# Motor_Driver.net
KiCad netlist of a schematic drawn in Altium Designer
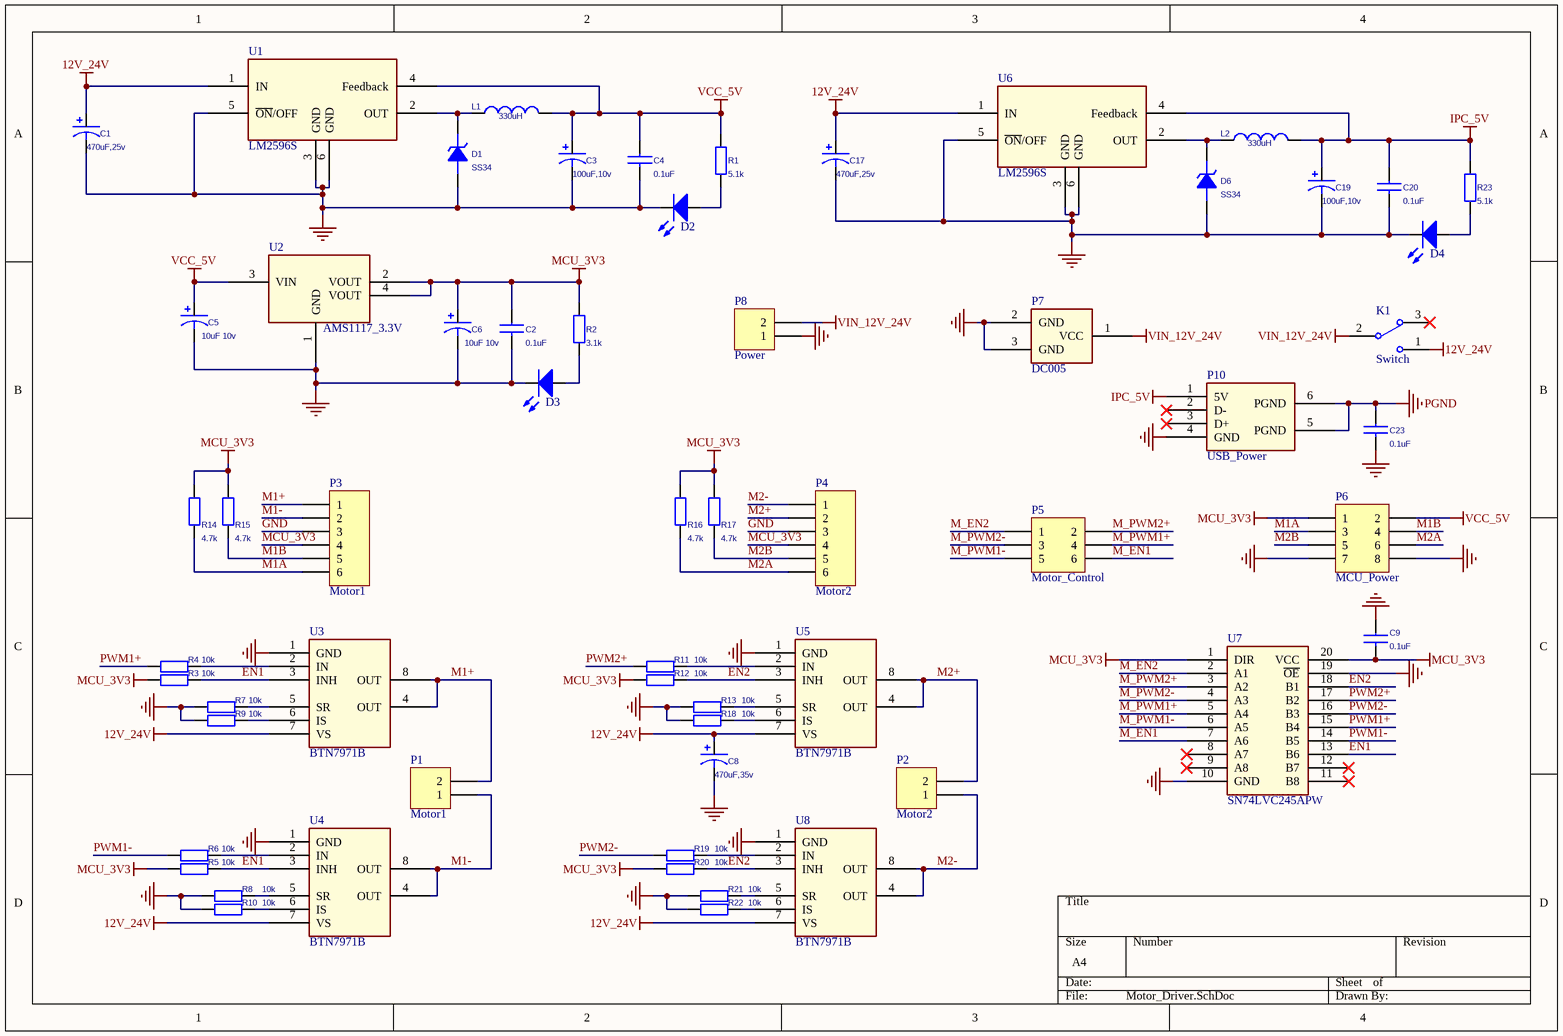
[diagram p0: Motor_Driver.SchDoc]

(export (version "E")
  (design (tool "Eeschema 10.0.6"))
  (components
    (comp (ref "C1")
      (value "470uF,25v")
      (footprint "SMD8102_C")
      (libsource (lib "My_Library") (part "Cap_Polar"))
    )
    (comp (ref "C2") (value "0.1uF") (libsource (lib "My_Library") (part "Cap")))
    (comp (ref "C3")
      (value "100uF,10v")
      (footprint "CAP_CASE_C_6032")
      (libsource (lib "My_Library") (part "Cap_Polar"))
    )
    (comp (ref "C4") (value "0.1uF") (libsource (lib "My_Library") (part "Cap")))
    (comp (ref "C5")
      (value "10uF 10v")
      (footprint "CAP_CASE_A_3216")
      (libsource (lib "My_Library") (part "Cap_Polar"))
    )
    (comp (ref "C6")
      (value "10uF 10v")
      (footprint "CAP_CASE_A_3216")
      (libsource (lib "My_Library") (part "Cap_Polar"))
    )
    (comp (ref "C8")
      (value "470uF,35v")
      (footprint "SMD8102_C")
      (libsource (lib "My_Library") (part "Cap_Polar"))
    )
    (comp (ref "C9") (value "0.1uF") (libsource (lib "My_Library") (part "Cap")))
    (comp (ref "C17")
      (value "470uF,25v")
      (footprint "SMD8102_C")
      (libsource (lib "My_Library") (part "Cap_Polar"))
    )
    (comp (ref "C19")
      (value "100uF,10v")
      (footprint "CAP_CASE_C_6032")
      (libsource (lib "My_Library") (part "Cap_Polar"))
    )
    (comp (ref "C20") (value "0.1uF") (libsource (lib "My_Library") (part "Cap")))
    (comp (ref "C23") (value "0.1uF") (libsource (lib "My_Library") (part "Cap")))
    (comp (ref "D1") (value "SS34") (libsource (lib "My_Library") (part "Diode_Zener")))
    (comp (ref "D2") (value "LED_0603") (footprint "0603_LED") (libsource (lib "My_Library") (part "LED")))
    (comp (ref "D3") (value "LED_0603") (footprint "0603_LED") (libsource (lib "My_Library") (part "LED")))
    (comp (ref "D4") (value "LED_0603") (footprint "0603_LED") (libsource (lib "My_Library") (part "LED")))
    (comp (ref "D6") (value "SS34") (libsource (lib "My_Library") (part "Diode_Zener")))
    (comp (ref "K1")
      (value "Switch")
      (footprint "Switch_Key3")
      (libsource (lib "My_Library") (part "Switch_Key3"))
    )
    (comp (ref "L1") (value "330uH") (libsource (lib "My_Library") (part "Inductor")))
    (comp (ref "L2") (value "330uH") (libsource (lib "My_Library") (part "Inductor")))
    (comp (ref "P1")
      (value "Motor1")
      (footprint "HT3.96_Power")
      (libsource (lib "My_Library") (part "HT3.96_Power"))
    )
    (comp (ref "P2")
      (value "Motor2")
      (footprint "HT3.96_Power")
      (libsource (lib "My_Library") (part "HT3.96_Power"))
    )
    (comp (ref "P3") (value "Motor1") (footprint "PH2.0_P6") (libsource (lib "My_Library") (part "PH2.0_P6")))
    (comp (ref "P4") (value "Motor2") (footprint "PH2.0_P6") (libsource (lib "My_Library") (part "PH2.0_P6")))
    (comp (ref "P5")
      (value "Motor_Control")
      (footprint "Connect_3×2")
      (libsource (lib "My_Library") (part "Connect_3×2"))
    )
    (comp (ref "P6")
      (value "MCU_Power")
      (footprint "CONNECT_4×2")
      (libsource (lib "My_Library") (part "Connect_4×2"))
    )
    (comp (ref "P7") (value "DC005") (footprint "DC005") (libsource (lib "My_Library") (part "DC005")))
    (comp (ref "P8")
      (value "Power")
      (footprint "HT3.96_Power")
      (libsource (lib "My_Library") (part "HT3.96_Power"))
    )
    (comp (ref "P10")
      (value "USB_Power")
      (footprint "USB_Pin6")
      (libsource (lib "My_Library") (part "USB_Pin6"))
    )
    (comp (ref "R1") (value "5.1k") (footprint "0805_R") (libsource (lib "My_Library") (part "Res")))
    (comp (ref "R2") (value "3.1k") (footprint "0805_R") (libsource (lib "My_Library") (part "Res")))
    (comp (ref "R3") (value "10k") (footprint "0805_R") (libsource (lib "") (part "Res_1")))
    (comp (ref "R4") (value "10k") (footprint "0805_R") (libsource (lib "") (part "Res_1")))
    (comp (ref "R5") (value "10k") (footprint "0805_R") (libsource (lib "") (part "Res_2")))
    (comp (ref "R6") (value "10k") (footprint "0805_R") (libsource (lib "") (part "Res_2")))
    (comp (ref "R7") (value "10k") (footprint "0805_R") (libsource (lib "") (part "Res_1")))
    (comp (ref "R8") (value "10k") (footprint "0805_R") (libsource (lib "") (part "Res_2")))
    (comp (ref "R9") (value "10k") (footprint "0805_R") (libsource (lib "") (part "Res_1")))
    (comp (ref "R10") (value "10k") (footprint "0805_R") (libsource (lib "") (part "Res_2")))
    (comp (ref "R11") (value "10k") (footprint "0805_R") (libsource (lib "") (part "Res_1")))
    (comp (ref "R12") (value "10k") (footprint "0805_R") (libsource (lib "") (part "Res_1")))
    (comp (ref "R13") (value "10k") (footprint "0805_R") (libsource (lib "") (part "Res_1")))
    (comp (ref "R14") (value "4.7k") (footprint "0805_R") (libsource (lib "My_Library") (part "Res")))
    (comp (ref "R15") (value "4.7k") (footprint "0805_R") (libsource (lib "My_Library") (part "Res")))
    (comp (ref "R16") (value "4.7k") (footprint "0805_R") (libsource (lib "My_Library") (part "Res")))
    (comp (ref "R17") (value "4.7k") (footprint "0805_R") (libsource (lib "My_Library") (part "Res")))
    (comp (ref "R18") (value "10k") (footprint "0805_R") (libsource (lib "") (part "Res_1")))
    (comp (ref "R19") (value "10k") (footprint "0805_R") (libsource (lib "") (part "Res_2")))
    (comp (ref "R20") (value "10k") (footprint "0805_R") (libsource (lib "") (part "Res_2")))
    (comp (ref "R21") (value "10k") (footprint "0805_R") (libsource (lib "") (part "Res_2")))
    (comp (ref "R22") (value "10k") (footprint "0805_R") (libsource (lib "") (part "Res_2")))
    (comp (ref "R23") (value "5.1k") (footprint "0805_R") (libsource (lib "My_Library") (part "Res")))
    (comp (ref "U1") (value "LM2596S") (footprint "LM2596S") (libsource (lib "My_Library") (part "LM2596S")))
    (comp (ref "U2")
      (value "AMS1117_3.3V")
      (footprint "LM1117")
      (libsource (lib "My_Library") (part "AMS1117_3.3V"))
    )
    (comp (ref "U3")
      (value "BTN7971B")
      (footprint "BTN7971B")
      (libsource (lib "My_Library") (part "BTN7971B"))
    )
    (comp (ref "U4")
      (value "BTN7971B")
      (footprint "BTN7971B")
      (libsource (lib "My_Library") (part "BTN7971B"))
    )
    (comp (ref "U5")
      (value "BTN7971B")
      (footprint "BTN7971B")
      (libsource (lib "My_Library") (part "BTN7971B"))
    )
    (comp (ref "U6") (value "LM2596S") (footprint "LM2596S") (libsource (lib "My_Library") (part "LM2596S")))
    (comp (ref "U7")
      (value "SN74LVC245APW")
      (footprint "SN74LVC245APW")
      (libsource (lib "My_Library") (part "SN74LVC245APW"))
    )
    (comp (ref "U8")
      (value "BTN7971B")
      (footprint "BTN7971B")
      (libsource (lib "My_Library") (part "BTN7971B"))
    )
  )
  (nets
    (net (code "1") (name "/EN1") (class "Default")
      (node (ref "R3") (pin "1") (pinfunction "1_1") (pintype "passive"))
      (node (ref "R5") (pin "2") (pinfunction "2_2") (pintype "passive"))
      (node (ref "U3") (pin "3") (pinfunction "INH_3") (pintype "passive"))
      (node (ref "U4") (pin "3") (pinfunction "INH_3") (pintype "passive"))
      (node (ref "U7") (pin "13") (pinfunction "B6_13") (pintype "passive"))
    )
    (net (code "2") (name "/EN2") (class "Default")
      (node (ref "R12") (pin "1") (pinfunction "1_1") (pintype "passive"))
      (node (ref "R20") (pin "2") (pinfunction "2_2") (pintype "passive"))
      (node (ref "U5") (pin "3") (pinfunction "INH_3") (pintype "passive"))
      (node (ref "U7") (pin "18") (pinfunction "B1_18") (pintype "passive"))
      (node (ref "U8") (pin "3") (pinfunction "INH_3") (pintype "passive"))
    )
    (net (code "3") (name "/M1+") (class "Default")
      (node (ref "P1") (pin "2") (pinfunction "2_2") (pintype "passive"))
      (node (ref "P3") (pin "1") (pinfunction "1_1") (pintype "passive"))
      (node (ref "U3") (pin "4") (pinfunction "OUT_4") (pintype "passive"))
      (node (ref "U3") (pin "8") (pinfunction "OUT_8") (pintype "passive"))
    )
    (net (code "4") (name "/M1-") (class "Default")
      (node (ref "P1") (pin "1") (pinfunction "1_1") (pintype "passive"))
      (node (ref "P3") (pin "2") (pinfunction "2_2") (pintype "passive"))
      (node (ref "U4") (pin "4") (pinfunction "OUT_4") (pintype "passive"))
      (node (ref "U4") (pin "8") (pinfunction "OUT_8") (pintype "passive"))
    )
    (net (code "5") (name "/M1A") (class "Default")
      (node (ref "P3") (pin "6") (pinfunction "6_6") (pintype "passive"))
      (node (ref "P6") (pin "3") (pinfunction "3_3") (pintype "passive"))
      (node (ref "R14") (pin "1") (pinfunction "1_1") (pintype "passive"))
    )
    (net (code "6") (name "/M1B") (class "Default")
      (node (ref "P3") (pin "5") (pinfunction "5_5") (pintype "passive"))
      (node (ref "P6") (pin "4") (pinfunction "4_4") (pintype "passive"))
      (node (ref "R15") (pin "1") (pinfunction "1_1") (pintype "passive"))
    )
    (net (code "7") (name "/M2+") (class "Default")
      (node (ref "P2") (pin "2") (pinfunction "2_2") (pintype "passive"))
      (node (ref "P4") (pin "2") (pinfunction "2_2") (pintype "passive"))
      (node (ref "U5") (pin "4") (pinfunction "OUT_4") (pintype "passive"))
      (node (ref "U5") (pin "8") (pinfunction "OUT_8") (pintype "passive"))
    )
    (net (code "8") (name "/M2-") (class "Default")
      (node (ref "P2") (pin "1") (pinfunction "1_1") (pintype "passive"))
      (node (ref "P4") (pin "1") (pinfunction "1_1") (pintype "passive"))
      (node (ref "U8") (pin "4") (pinfunction "OUT_4") (pintype "passive"))
      (node (ref "U8") (pin "8") (pinfunction "OUT_8") (pintype "passive"))
    )
    (net (code "9") (name "/M2A") (class "Default")
      (node (ref "P4") (pin "6") (pinfunction "6_6") (pintype "passive"))
      (node (ref "P6") (pin "6") (pinfunction "6_6") (pintype "passive"))
      (node (ref "R16") (pin "1") (pinfunction "1_1") (pintype "passive"))
    )
    (net (code "10") (name "/M2B") (class "Default")
      (node (ref "P4") (pin "5") (pinfunction "5_5") (pintype "passive"))
      (node (ref "P6") (pin "5") (pinfunction "5_5") (pintype "passive"))
      (node (ref "R17") (pin "1") (pinfunction "1_1") (pintype "passive"))
    )
    (net (code "11") (name "/M_EN1") (class "Default")
      (node (ref "P5") (pin "6") (pinfunction "6_6") (pintype "passive"))
      (node (ref "U7") (pin "7") (pinfunction "A6_7") (pintype "passive"))
    )
    (net (code "12") (name "/M_EN2") (class "Default")
      (node (ref "P5") (pin "1") (pinfunction "1_1") (pintype "passive"))
      (node (ref "U7") (pin "2") (pinfunction "A1_2") (pintype "passive"))
    )
    (net (code "13") (name "/M_PWM1+") (class "Default")
      (node (ref "P5") (pin "4") (pinfunction "4_4") (pintype "passive"))
      (node (ref "U7") (pin "5") (pinfunction "A4_5") (pintype "passive"))
    )
    (net (code "14") (name "/M_PWM1-") (class "Default")
      (node (ref "P5") (pin "5") (pinfunction "5_5") (pintype "passive"))
      (node (ref "U7") (pin "6") (pinfunction "A5_6") (pintype "passive"))
    )
    (net (code "15") (name "/M_PWM2+") (class "Default")
      (node (ref "P5") (pin "2") (pinfunction "2_2") (pintype "passive"))
      (node (ref "U7") (pin "3") (pinfunction "A2_3") (pintype "passive"))
    )
    (net (code "16") (name "/M_PWM2-") (class "Default")
      (node (ref "P5") (pin "3") (pinfunction "3_3") (pintype "passive"))
      (node (ref "U7") (pin "4") (pinfunction "A3_4") (pintype "passive"))
    )
    (net (code "17") (name "/PWM1+") (class "Default")
      (node (ref "R4") (pin "2") (pinfunction "2_2") (pintype "passive"))
      (node (ref "U7") (pin "15") (pinfunction "B4_15") (pintype "passive"))
    )
    (net (code "18") (name "/PWM1-") (class "Default")
      (node (ref "R6") (pin "1") (pinfunction "1_1") (pintype "passive"))
      (node (ref "U7") (pin "14") (pinfunction "B5_14") (pintype "passive"))
    )
    (net (code "19") (name "/PWM2+") (class "Default")
      (node (ref "R11") (pin "2") (pinfunction "2_2") (pintype "passive"))
      (node (ref "U7") (pin "17") (pinfunction "B2_17") (pintype "passive"))
    )
    (net (code "20") (name "/PWM2-") (class "Default")
      (node (ref "R19") (pin "1") (pinfunction "1_1") (pintype "passive"))
      (node (ref "U7") (pin "16") (pinfunction "B3_16") (pintype "passive"))
    )
    (net (code "21") (name "12V_24V") (class "Default")
      (node (ref "C1") (pin "1") (pinfunction "1_1") (pintype "passive"))
      (node (ref "C17") (pin "1") (pinfunction "1_1") (pintype "passive"))
      (node (ref "C8") (pin "1") (pinfunction "1_1") (pintype "passive"))
      (node (ref "K1") (pin "1") (pinfunction "1_1") (pintype "passive"))
      (node (ref "U1") (pin "1") (pinfunction "IN_1") (pintype "passive"))
      (node (ref "U3") (pin "7") (pinfunction "VS_7") (pintype "passive"))
      (node (ref "U4") (pin "7") (pinfunction "VS_7") (pintype "passive"))
      (node (ref "U5") (pin "7") (pinfunction "VS_7") (pintype "passive"))
      (node (ref "U6") (pin "1") (pinfunction "IN_1") (pintype "passive"))
      (node (ref "U8") (pin "7") (pinfunction "VS_7") (pintype "passive"))
    )
    (net (code "22") (name "GND") (class "Default")
      (node (ref "C1") (pin "2") (pinfunction "2_2") (pintype "passive"))
      (node (ref "C17") (pin "2") (pinfunction "2_2") (pintype "passive"))
      (node (ref "C19") (pin "2") (pinfunction "2_2") (pintype "passive"))
      (node (ref "C2") (pin "2") (pinfunction "2_2") (pintype "passive"))
      (node (ref "C20") (pin "2") (pinfunction "2_2") (pintype "passive"))
      (node (ref "C23") (pin "2") (pinfunction "2_2") (pintype "passive"))
      (node (ref "C3") (pin "2") (pinfunction "2_2") (pintype "passive"))
      (node (ref "C4") (pin "2") (pinfunction "2_2") (pintype "passive"))
      (node (ref "C5") (pin "2") (pinfunction "2_2") (pintype "passive"))
      (node (ref "C6") (pin "2") (pinfunction "2_2") (pintype "passive"))
      (node (ref "C8") (pin "2") (pinfunction "2_2") (pintype "passive"))
      (node (ref "C9") (pin "1") (pinfunction "1_1") (pintype "passive"))
      (node (ref "D1") (pin "2") (pinfunction "ANODE_2") (pintype "passive"))
      (node (ref "D2") (pin "K") (pinfunction "K_K") (pintype "passive"))
      (node (ref "D3") (pin "K") (pinfunction "K_K") (pintype "passive"))
      (node (ref "D4") (pin "K") (pinfunction "K_K") (pintype "passive"))
      (node (ref "D6") (pin "2") (pinfunction "ANODE_2") (pintype "passive"))
      (node (ref "P10") (pin "4") (pinfunction "GND_4") (pintype "passive"))
      (node (ref "P3") (pin "3") (pinfunction "3_3") (pintype "passive"))
      (node (ref "P4") (pin "3") (pinfunction "3_3") (pintype "passive"))
      (node (ref "P6") (pin "7") (pinfunction "7_7") (pintype "passive"))
      (node (ref "P6") (pin "8") (pinfunction "8_8") (pintype "passive"))
      (node (ref "P7") (pin "2") (pinfunction "GND_2") (pintype "passive"))
      (node (ref "P7") (pin "3") (pinfunction "GND_3") (pintype "passive"))
      (node (ref "P8") (pin "1") (pinfunction "1_1") (pintype "passive"))
      (node (ref "R10") (pin "1") (pinfunction "1_1") (pintype "passive"))
      (node (ref "R13") (pin "2") (pinfunction "2_2") (pintype "passive"))
      (node (ref "R18") (pin "2") (pinfunction "2_2") (pintype "passive"))
      (node (ref "R21") (pin "1") (pinfunction "1_1") (pintype "passive"))
      (node (ref "R22") (pin "1") (pinfunction "1_1") (pintype "passive"))
      (node (ref "R7") (pin "2") (pinfunction "2_2") (pintype "passive"))
      (node (ref "R8") (pin "1") (pinfunction "1_1") (pintype "passive"))
      (node (ref "R9") (pin "2") (pinfunction "2_2") (pintype "passive"))
      (node (ref "U1") (pin "3") (pinfunction "GND_3") (pintype "passive"))
      (node (ref "U1") (pin "5") (pinfunction "~{ON}/OFF_5") (pintype "passive"))
      (node (ref "U1") (pin "6") (pinfunction "GND_6") (pintype "passive"))
      (node (ref "U2") (pin "1") (pinfunction "GND_1") (pintype "passive"))
      (node (ref "U3") (pin "1") (pinfunction "GND_1") (pintype "passive"))
      (node (ref "U4") (pin "1") (pinfunction "GND_1") (pintype "passive"))
      (node (ref "U5") (pin "1") (pinfunction "GND_1") (pintype "passive"))
      (node (ref "U6") (pin "3") (pinfunction "GND_3") (pintype "passive"))
      (node (ref "U6") (pin "5") (pinfunction "~{ON}/OFF_5") (pintype "passive"))
      (node (ref "U6") (pin "6") (pinfunction "GND_6") (pintype "passive"))
      (node (ref "U7") (pin "10") (pinfunction "GND_10") (pintype "passive"))
      (node (ref "U7") (pin "19") (pinfunction "~{OE}_19") (pintype "passive"))
      (node (ref "U8") (pin "1") (pinfunction "GND_1") (pintype "passive"))
    )
    (net (code "23") (name "IPC_5V") (class "Default")
      (node (ref "C19") (pin "1") (pinfunction "1_1") (pintype "passive"))
      (node (ref "C20") (pin "1") (pinfunction "1_1") (pintype "passive"))
      (node (ref "L2") (pin "2") (pinfunction "2_2") (pintype "passive"))
      (node (ref "P10") (pin "1") (pinfunction "5V_1") (pintype "passive"))
      (node (ref "R23") (pin "2") (pinfunction "2_2") (pintype "passive"))
      (node (ref "U6") (pin "4") (pinfunction "Feedback_4") (pintype "passive"))
    )
    (net (code "24") (name "MCU_3V3") (class "Default")
      (node (ref "C2") (pin "1") (pinfunction "1_1") (pintype "passive"))
      (node (ref "C6") (pin "1") (pinfunction "1_1") (pintype "passive"))
      (node (ref "C9") (pin "2") (pinfunction "2_2") (pintype "passive"))
      (node (ref "P3") (pin "4") (pinfunction "4_4") (pintype "passive"))
      (node (ref "P4") (pin "4") (pinfunction "4_4") (pintype "passive"))
      (node (ref "P6") (pin "1") (pinfunction "1_1") (pintype "passive"))
      (node (ref "R12") (pin "2") (pinfunction "2_2") (pintype "passive"))
      (node (ref "R14") (pin "2") (pinfunction "2_2") (pintype "passive"))
      (node (ref "R15") (pin "2") (pinfunction "2_2") (pintype "passive"))
      (node (ref "R16") (pin "2") (pinfunction "2_2") (pintype "passive"))
      (node (ref "R17") (pin "2") (pinfunction "2_2") (pintype "passive"))
      (node (ref "R2") (pin "2") (pinfunction "2_2") (pintype "passive"))
      (node (ref "R20") (pin "1") (pinfunction "1_1") (pintype "passive"))
      (node (ref "R3") (pin "2") (pinfunction "2_2") (pintype "passive"))
      (node (ref "R5") (pin "1") (pinfunction "1_1") (pintype "passive"))
      (node (ref "U2") (pin "2") (pinfunction "VOUT_2") (pintype "passive"))
      (node (ref "U2") (pin "4") (pinfunction "VOUT_4") (pintype "passive"))
      (node (ref "U7") (pin "1") (pinfunction "DIR_1") (pintype "passive"))
      (node (ref "U7") (pin "20") (pinfunction "VCC_20") (pintype "passive"))
    )
    (net (code "25") (name "Net-(D1-CATHODE)") (class "Default")
      (node (ref "D1") (pin "1") (pinfunction "CATHODE_1") (pintype "passive"))
      (node (ref "L1") (pin "1") (pinfunction "1_1") (pintype "passive"))
      (node (ref "U1") (pin "2") (pinfunction "OUT_2") (pintype "passive"))
    )
    (net (code "26") (name "Net-(D2-PadA)") (class "Default")
      (node (ref "D2") (pin "A") (pinfunction "A_A") (pintype "passive"))
      (node (ref "R1") (pin "1") (pinfunction "1_1") (pintype "passive"))
    )
    (net (code "27") (name "Net-(D3-PadA)") (class "Default")
      (node (ref "D3") (pin "A") (pinfunction "A_A") (pintype "passive"))
      (node (ref "R2") (pin "1") (pinfunction "1_1") (pintype "passive"))
    )
    (net (code "28") (name "Net-(D4-PadA)") (class "Default")
      (node (ref "D4") (pin "A") (pinfunction "A_A") (pintype "passive"))
      (node (ref "R23") (pin "1") (pinfunction "1_1") (pintype "passive"))
    )
    (net (code "29") (name "Net-(D6-CATHODE)") (class "Default")
      (node (ref "D6") (pin "1") (pinfunction "CATHODE_1") (pintype "passive"))
      (node (ref "L2") (pin "1") (pinfunction "1_1") (pintype "passive"))
      (node (ref "U6") (pin "2") (pinfunction "OUT_2") (pintype "passive"))
    )
    (net (code "30") (name "Net-(U3-IN)") (class "Default")
      (node (ref "R4") (pin "1") (pinfunction "1_1") (pintype "passive"))
      (node (ref "U3") (pin "2") (pinfunction "IN_2") (pintype "passive"))
    )
    (net (code "31") (name "Net-(U3-IS)") (class "Default")
      (node (ref "R9") (pin "1") (pinfunction "1_1") (pintype "passive"))
      (node (ref "U3") (pin "6") (pinfunction "IS_6") (pintype "passive"))
    )
    (net (code "32") (name "Net-(U3-SR)") (class "Default")
      (node (ref "R7") (pin "1") (pinfunction "1_1") (pintype "passive"))
      (node (ref "U3") (pin "5") (pinfunction "SR_5") (pintype "passive"))
    )
    (net (code "33") (name "Net-(U4-IN)") (class "Default")
      (node (ref "R6") (pin "2") (pinfunction "2_2") (pintype "passive"))
      (node (ref "U4") (pin "2") (pinfunction "IN_2") (pintype "passive"))
    )
    (net (code "34") (name "Net-(U4-IS)") (class "Default")
      (node (ref "R10") (pin "2") (pinfunction "2_2") (pintype "passive"))
      (node (ref "U4") (pin "6") (pinfunction "IS_6") (pintype "passive"))
    )
    (net (code "35") (name "Net-(U4-SR)") (class "Default")
      (node (ref "R8") (pin "2") (pinfunction "2_2") (pintype "passive"))
      (node (ref "U4") (pin "5") (pinfunction "SR_5") (pintype "passive"))
    )
    (net (code "36") (name "Net-(U5-IN)") (class "Default")
      (node (ref "R11") (pin "1") (pinfunction "1_1") (pintype "passive"))
      (node (ref "U5") (pin "2") (pinfunction "IN_2") (pintype "passive"))
    )
    (net (code "37") (name "Net-(U5-IS)") (class "Default")
      (node (ref "R18") (pin "1") (pinfunction "1_1") (pintype "passive"))
      (node (ref "U5") (pin "6") (pinfunction "IS_6") (pintype "passive"))
    )
    (net (code "38") (name "Net-(U5-SR)") (class "Default")
      (node (ref "R13") (pin "1") (pinfunction "1_1") (pintype "passive"))
      (node (ref "U5") (pin "5") (pinfunction "SR_5") (pintype "passive"))
    )
    (net (code "39") (name "Net-(U8-IN)") (class "Default")
      (node (ref "R19") (pin "2") (pinfunction "2_2") (pintype "passive"))
      (node (ref "U8") (pin "2") (pinfunction "IN_2") (pintype "passive"))
    )
    (net (code "40") (name "Net-(U8-IS)") (class "Default")
      (node (ref "R22") (pin "2") (pinfunction "2_2") (pintype "passive"))
      (node (ref "U8") (pin "6") (pinfunction "IS_6") (pintype "passive"))
    )
    (net (code "41") (name "Net-(U8-SR)") (class "Default")
      (node (ref "R21") (pin "2") (pinfunction "2_2") (pintype "passive"))
      (node (ref "U8") (pin "5") (pinfunction "SR_5") (pintype "passive"))
    )
    (net (code "42") (name "PGND") (class "Default")
      (node (ref "C23") (pin "1") (pinfunction "1_1") (pintype "passive"))
      (node (ref "P10") (pin "5") (pinfunction "PGND_5") (pintype "passive"))
      (node (ref "P10") (pin "6") (pinfunction "PGND_6") (pintype "passive"))
    )
    (net (code "43") (name "VCC_5V") (class "Default")
      (node (ref "C3") (pin "1") (pinfunction "1_1") (pintype "passive"))
      (node (ref "C4") (pin "1") (pinfunction "1_1") (pintype "passive"))
      (node (ref "C5") (pin "1") (pinfunction "1_1") (pintype "passive"))
      (node (ref "L1") (pin "2") (pinfunction "2_2") (pintype "passive"))
      (node (ref "P6") (pin "2") (pinfunction "2_2") (pintype "passive"))
      (node (ref "R1") (pin "2") (pinfunction "2_2") (pintype "passive"))
      (node (ref "U1") (pin "4") (pinfunction "Feedback_4") (pintype "passive"))
      (node (ref "U2") (pin "3") (pinfunction "VIN_3") (pintype "passive"))
    )
    (net (code "44") (name "VIN_12V_24V") (class "Default")
      (node (ref "K1") (pin "2") (pinfunction "2_2") (pintype "passive"))
      (node (ref "P7") (pin "1") (pinfunction "VCC_1") (pintype "passive"))
      (node (ref "P8") (pin "2") (pinfunction "2_2") (pintype "passive"))
    )
    (net (code "45") (name "unconnected-(K1-Pad3)") (class "Default")
      (node (ref "K1") (pin "3") (pinfunction "3_3") (pintype "passive+no_connect"))
    )
    (net (code "46") (name "unconnected-(P10-D+-Pad3)") (class "Default")
      (node (ref "P10") (pin "3") (pinfunction "D+_3") (pintype "passive+no_connect"))
    )
    (net (code "47") (name "unconnected-(P10-D--Pad2)") (class "Default")
      (node (ref "P10") (pin "2") (pinfunction "D-_2") (pintype "passive+no_connect"))
    )
    (net (code "48") (name "unconnected-(U7-A7-Pad8)") (class "Default")
      (node (ref "U7") (pin "8") (pinfunction "A7_8") (pintype "passive+no_connect"))
    )
    (net (code "49") (name "unconnected-(U7-A8-Pad9)") (class "Default")
      (node (ref "U7") (pin "9") (pinfunction "A8_9") (pintype "passive+no_connect"))
    )
    (net (code "50") (name "unconnected-(U7-B7-Pad12)") (class "Default")
      (node (ref "U7") (pin "12") (pinfunction "B7_12") (pintype "passive+no_connect"))
    )
    (net (code "51") (name "unconnected-(U7-B8-Pad11)") (class "Default")
      (node (ref "U7") (pin "11") (pinfunction "B8_11") (pintype "passive+no_connect"))
    )
  )
)
